# pcbgrado.net
KiCad netlist of a schematic drawn in EAGLE
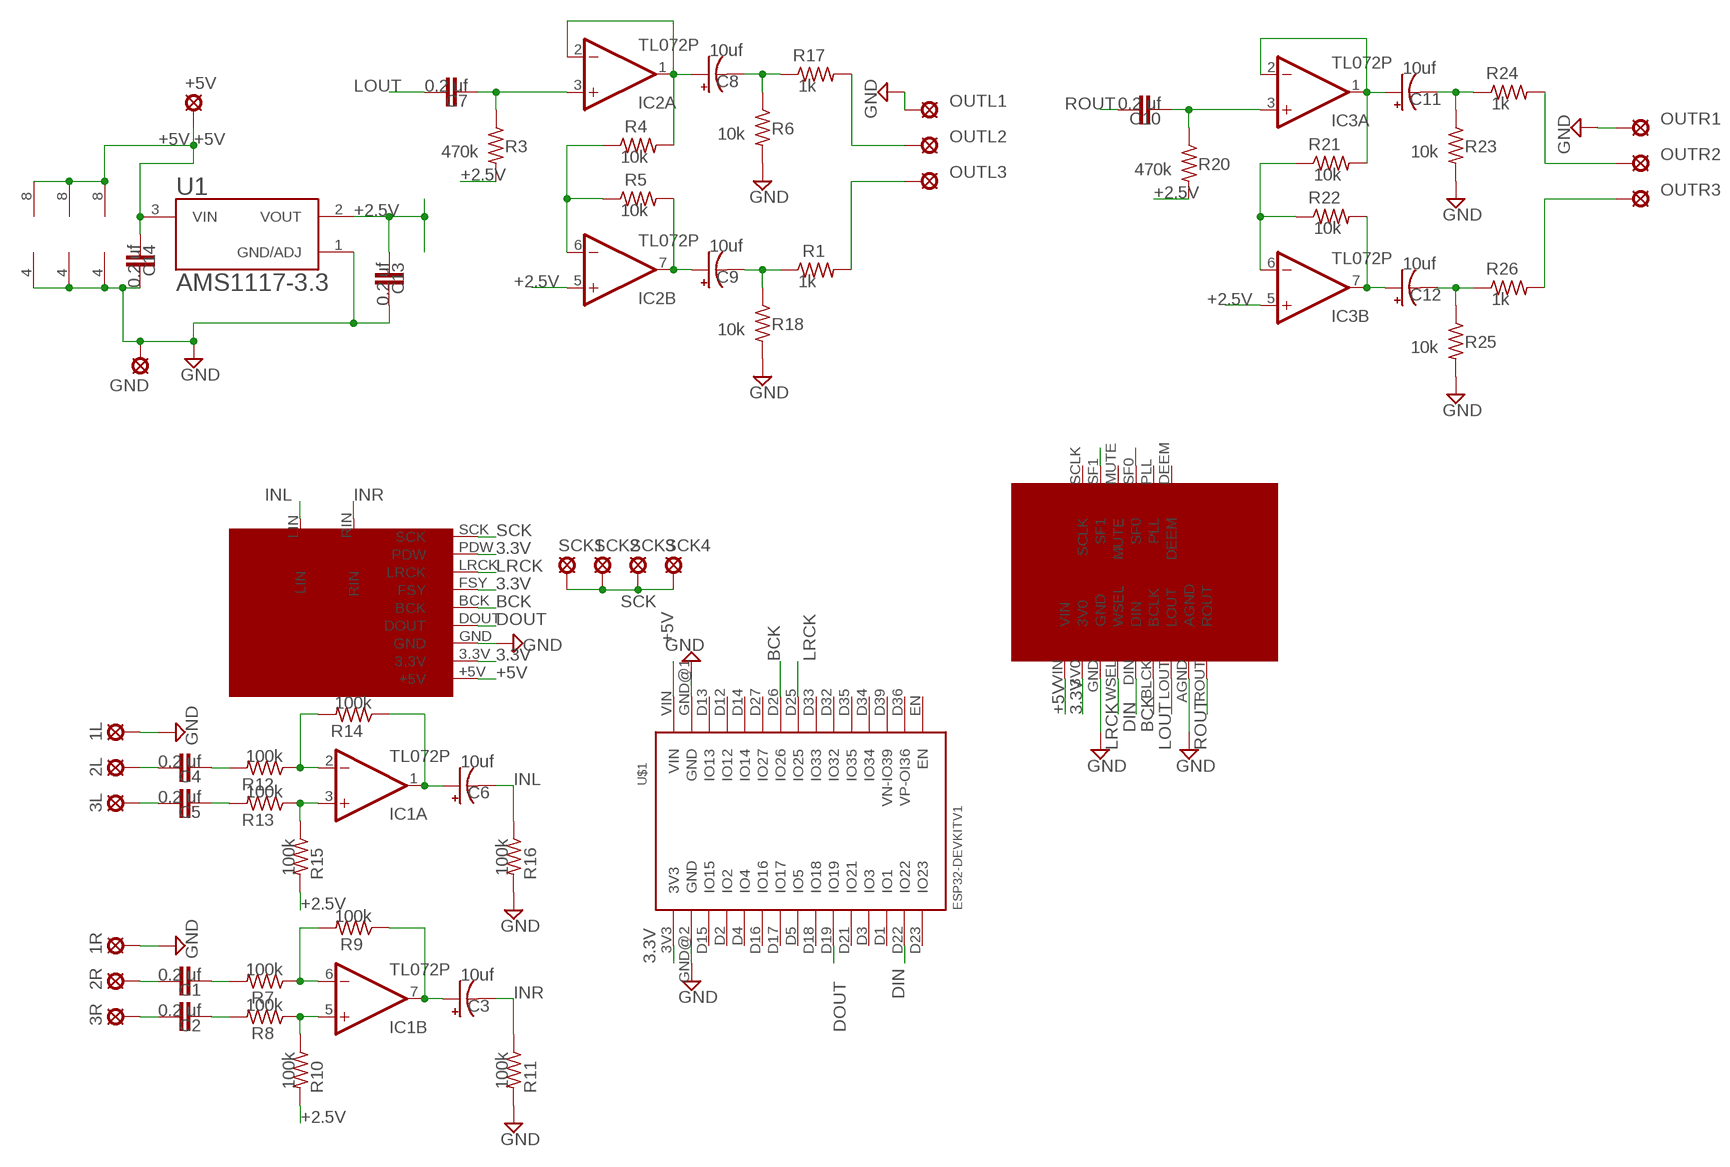
[diagram p0: schematic, sheet 1]

(export (version "E")
  (design (tool "Eeschema 10.0.6"))
  (components
    (comp (ref "+5V")
      (value "LSP10")
      (footprint "eagle-import:LSP10")
      (libsource (lib "eagle-import") (part "LSP10"))
    )
    (comp (ref "1L")
      (value "LSP10")
      (footprint "eagle-import:LSP10")
      (libsource (lib "eagle-import") (part "LSP10"))
    )
    (comp (ref "1R")
      (value "LSP10")
      (footprint "eagle-import:LSP10")
      (libsource (lib "eagle-import") (part "LSP10"))
    )
    (comp (ref "2L")
      (value "LSP10")
      (footprint "eagle-import:LSP10")
      (libsource (lib "eagle-import") (part "LSP10"))
    )
    (comp (ref "2R")
      (value "LSP10")
      (footprint "eagle-import:LSP10")
      (libsource (lib "eagle-import") (part "LSP10"))
    )
    (comp (ref "3L")
      (value "LSP10")
      (footprint "eagle-import:LSP10")
      (libsource (lib "eagle-import") (part "LSP10"))
    )
    (comp (ref "3R")
      (value "LSP10")
      (footprint "eagle-import:LSP10")
      (libsource (lib "eagle-import") (part "LSP10"))
    )
    (comp (ref "C1")
      (value "C-EU025-025X050")
      (footprint "eagle-import:C025-025X050")
      (fields (field (name "POPULARITY") "65") (field (name "POPULARITY_1") "0.2 uf"))
      (libsource (lib "eagle-import") (part "C-EU025-025X050"))
    )
    (comp (ref "C2")
      (value "C-EU025-025X050")
      (footprint "eagle-import:C025-025X050")
      (fields (field (name "POPULARITY") "65") (field (name "POPULARITY_1") "0.2 uf"))
      (libsource (lib "eagle-import") (part "C-EU025-025X050"))
    )
    (comp (ref "C3")
      (value "CPOL-USE1.8-4")
      (footprint "eagle-import:E1,8-4")
      (fields (field (name "POPULARITY") "6") (field (name "POPULARITY_1") "10uf"))
      (libsource (lib "eagle-import") (part "CPOL-USE1.8-4"))
    )
    (comp (ref "C4")
      (value "C-EU025-025X050")
      (footprint "eagle-import:C025-025X050")
      (fields (field (name "POPULARITY") "65") (field (name "POPULARITY_1") "0.2 uf"))
      (libsource (lib "eagle-import") (part "C-EU025-025X050"))
    )
    (comp (ref "C5")
      (value "C-EU025-025X050")
      (footprint "eagle-import:C025-025X050")
      (fields (field (name "POPULARITY") "65") (field (name "POPULARITY_1") "0.2 uf"))
      (libsource (lib "eagle-import") (part "C-EU025-025X050"))
    )
    (comp (ref "C6")
      (value "CPOL-USE1.8-4")
      (footprint "eagle-import:E1,8-4")
      (fields (field (name "POPULARITY") "6") (field (name "POPULARITY_1") "10uf"))
      (libsource (lib "eagle-import") (part "CPOL-USE1.8-4"))
    )
    (comp (ref "C7")
      (value "C-EU025-030X050")
      (footprint "eagle-import:C025-030X050")
      (fields (field (name "POPULARITY") "14") (field (name "POPULARITY_1") "0.2 uf"))
      (libsource (lib "eagle-import") (part "C-EU025-030X050"))
    )
    (comp (ref "C8")
      (value "CPOL-USE1.8-4")
      (footprint "eagle-import:E1,8-4")
      (fields (field (name "POPULARITY") "6") (field (name "POPULARITY_1") "10uf"))
      (libsource (lib "eagle-import") (part "CPOL-USE1.8-4"))
    )
    (comp (ref "C9")
      (value "CPOL-USE1.8-4")
      (footprint "eagle-import:E1,8-4")
      (fields (field (name "POPULARITY") "6") (field (name "POPULARITY_1") "10uf"))
      (libsource (lib "eagle-import") (part "CPOL-USE1.8-4"))
    )
    (comp (ref "C10")
      (value "C-EU025-030X050")
      (footprint "eagle-import:C025-030X050")
      (fields (field (name "POPULARITY") "14") (field (name "POPULARITY_1") "0.2 uf"))
      (libsource (lib "eagle-import") (part "C-EU025-030X050"))
    )
    (comp (ref "C11")
      (value "CPOL-USE1.8-4")
      (footprint "eagle-import:E1,8-4")
      (fields (field (name "POPULARITY") "6") (field (name "POPULARITY_1") "10uf"))
      (libsource (lib "eagle-import") (part "CPOL-USE1.8-4"))
    )
    (comp (ref "C12")
      (value "CPOL-USE1.8-4")
      (footprint "eagle-import:E1,8-4")
      (fields (field (name "POPULARITY") "6") (field (name "POPULARITY_1") "10uf"))
      (libsource (lib "eagle-import") (part "CPOL-USE1.8-4"))
    )
    (comp (ref "C13")
      (value "C-EU025-025X050")
      (footprint "eagle-import:C025-025X050")
      (fields (field (name "POPULARITY") "65") (field (name "POPULARITY_1") "0.2 uf"))
      (libsource (lib "eagle-import") (part "C-EU025-025X050"))
    )
    (comp (ref "C14")
      (value "C-EU025-025X050")
      (footprint "eagle-import:C025-025X050")
      (fields (field (name "POPULARITY") "65") (field (name "POPULARITY_1") "0.2 uf"))
      (libsource (lib "eagle-import") (part "C-EU025-025X050"))
    )
    (comp (ref "GND")
      (value "LSP10")
      (footprint "eagle-import:LSP10")
      (libsource (lib "eagle-import") (part "LSP10"))
    )
    (comp (ref "IC1")
      (value "TL072P")
      (footprint "eagle-import:DIL08")
      (libsource (lib "eagle-import") (part "TL072P"))
    )
    (comp (ref "IC2")
      (value "TL072P")
      (footprint "eagle-import:DIL08")
      (libsource (lib "eagle-import") (part "TL072P"))
    )
    (comp (ref "IC3")
      (value "TL072P")
      (footprint "eagle-import:DIL08")
      (libsource (lib "eagle-import") (part "TL072P"))
    )
    (comp (ref "OUTL1")
      (value "LSP10")
      (footprint "eagle-import:LSP10")
      (libsource (lib "eagle-import") (part "LSP10"))
    )
    (comp (ref "OUTL2")
      (value "LSP10")
      (footprint "eagle-import:LSP10")
      (libsource (lib "eagle-import") (part "LSP10"))
    )
    (comp (ref "OUTL3")
      (value "LSP10")
      (footprint "eagle-import:LSP10")
      (libsource (lib "eagle-import") (part "LSP10"))
    )
    (comp (ref "OUTR1")
      (value "LSP10")
      (footprint "eagle-import:LSP10")
      (libsource (lib "eagle-import") (part "LSP10"))
    )
    (comp (ref "OUTR2")
      (value "LSP10")
      (footprint "eagle-import:LSP10")
      (libsource (lib "eagle-import") (part "LSP10"))
    )
    (comp (ref "OUTR3")
      (value "LSP10")
      (footprint "eagle-import:LSP10")
      (libsource (lib "eagle-import") (part "LSP10"))
    )
    (comp (ref "R1")
      (value "R-US_0204/7")
      (footprint "eagle-import:0204_7")
      (fields (field (name "POPULARITY") "48") (field (name "POPULARITY_1") "1k"))
      (libsource (lib "eagle-import") (part "R-US_0204/7"))
    )
    (comp (ref "R3")
      (value "R-US_0204/7")
      (footprint "eagle-import:0204_7")
      (fields (field (name "POPULARITY") "48") (field (name "POPULARITY_1") "470k"))
      (libsource (lib "eagle-import") (part "R-US_0204/7"))
    )
    (comp (ref "R4")
      (value "R-US_0204/7")
      (footprint "eagle-import:0204_7")
      (fields (field (name "POPULARITY") "48") (field (name "POPULARITY_1") "10k"))
      (libsource (lib "eagle-import") (part "R-US_0204/7"))
    )
    (comp (ref "R5")
      (value "R-US_0204/7")
      (footprint "eagle-import:0204_7")
      (fields (field (name "POPULARITY") "48") (field (name "POPULARITY_1") "10k"))
      (libsource (lib "eagle-import") (part "R-US_0204/7"))
    )
    (comp (ref "R6")
      (value "R-US_0204/7")
      (footprint "eagle-import:0204_7")
      (fields (field (name "POPULARITY") "48") (field (name "POPULARITY_1") "10k"))
      (libsource (lib "eagle-import") (part "R-US_0204/7"))
    )
    (comp (ref "R7")
      (value "R-US_0204/7")
      (footprint "eagle-import:0204_7")
      (fields (field (name "POPULARITY") "48") (field (name "POPULARITY_1") "100k"))
      (libsource (lib "eagle-import") (part "R-US_0204/7"))
    )
    (comp (ref "R8")
      (value "R-US_0204/7")
      (footprint "eagle-import:0204_7")
      (fields (field (name "POPULARITY") "48") (field (name "POPULARITY_1") "100k"))
      (libsource (lib "eagle-import") (part "R-US_0204/7"))
    )
    (comp (ref "R9")
      (value "R-US_0204/7")
      (footprint "eagle-import:0204_7")
      (fields (field (name "POPULARITY") "48") (field (name "POPULARITY_1") "100k"))
      (libsource (lib "eagle-import") (part "R-US_0204/7"))
    )
    (comp (ref "R10")
      (value "R-US_0204/7")
      (footprint "eagle-import:0204_7")
      (fields (field (name "POPULARITY") "48") (field (name "POPULARITY_1") "100k"))
      (libsource (lib "eagle-import") (part "R-US_0204/7"))
    )
    (comp (ref "R11")
      (value "R-US_0204/7")
      (footprint "eagle-import:0204_7")
      (fields (field (name "POPULARITY") "48") (field (name "POPULARITY_1") "100k"))
      (libsource (lib "eagle-import") (part "R-US_0204/7"))
    )
    (comp (ref "R12")
      (value "R-US_0204/7")
      (footprint "eagle-import:0204_7")
      (fields (field (name "POPULARITY") "48") (field (name "POPULARITY_1") "100k"))
      (libsource (lib "eagle-import") (part "R-US_0204/7"))
    )
    (comp (ref "R13")
      (value "R-US_0204/7")
      (footprint "eagle-import:0204_7")
      (fields (field (name "POPULARITY") "48") (field (name "POPULARITY_1") "100k"))
      (libsource (lib "eagle-import") (part "R-US_0204/7"))
    )
    (comp (ref "R14")
      (value "R-US_0204/7")
      (footprint "eagle-import:0204_7")
      (fields (field (name "POPULARITY") "48") (field (name "POPULARITY_1") "100k"))
      (libsource (lib "eagle-import") (part "R-US_0204/7"))
    )
    (comp (ref "R15")
      (value "R-US_0204/7")
      (footprint "eagle-import:0204_7")
      (fields (field (name "POPULARITY") "48") (field (name "POPULARITY_1") "100k"))
      (libsource (lib "eagle-import") (part "R-US_0204/7"))
    )
    (comp (ref "R16")
      (value "R-US_0204/7")
      (footprint "eagle-import:0204_7")
      (fields (field (name "POPULARITY") "48") (field (name "POPULARITY_1") "100k"))
      (libsource (lib "eagle-import") (part "R-US_0204/7"))
    )
    (comp (ref "R17")
      (value "R-US_0204/7")
      (footprint "eagle-import:0204_7")
      (fields (field (name "POPULARITY") "48") (field (name "POPULARITY_1") "1k"))
      (libsource (lib "eagle-import") (part "R-US_0204/7"))
    )
    (comp (ref "R18")
      (value "R-US_0204/7")
      (footprint "eagle-import:0204_7")
      (fields (field (name "POPULARITY") "48") (field (name "POPULARITY_1") "10k"))
      (libsource (lib "eagle-import") (part "R-US_0204/7"))
    )
    (comp (ref "R20")
      (value "R-US_0204/7")
      (footprint "eagle-import:0204_7")
      (fields (field (name "POPULARITY") "48") (field (name "POPULARITY_1") "470k"))
      (libsource (lib "eagle-import") (part "R-US_0204/7"))
    )
    (comp (ref "R21")
      (value "R-US_0204/7")
      (footprint "eagle-import:0204_7")
      (fields (field (name "POPULARITY") "48") (field (name "POPULARITY_1") "10k"))
      (libsource (lib "eagle-import") (part "R-US_0204/7"))
    )
    (comp (ref "R22")
      (value "R-US_0204/7")
      (footprint "eagle-import:0204_7")
      (fields (field (name "POPULARITY") "48") (field (name "POPULARITY_1") "10k"))
      (libsource (lib "eagle-import") (part "R-US_0204/7"))
    )
    (comp (ref "R23")
      (value "R-US_0204/7")
      (footprint "eagle-import:0204_7")
      (fields (field (name "POPULARITY") "48") (field (name "POPULARITY_1") "10k"))
      (libsource (lib "eagle-import") (part "R-US_0204/7"))
    )
    (comp (ref "R24")
      (value "R-US_0204/7")
      (footprint "eagle-import:0204_7")
      (fields (field (name "POPULARITY") "48") (field (name "POPULARITY_1") "1k"))
      (libsource (lib "eagle-import") (part "R-US_0204/7"))
    )
    (comp (ref "R25")
      (value "R-US_0204/7")
      (footprint "eagle-import:0204_7")
      (fields (field (name "POPULARITY") "48") (field (name "POPULARITY_1") "10k"))
      (libsource (lib "eagle-import") (part "R-US_0204/7"))
    )
    (comp (ref "R26")
      (value "R-US_0204/7")
      (footprint "eagle-import:0204_7")
      (fields (field (name "POPULARITY") "48") (field (name "POPULARITY_1") "1k"))
      (libsource (lib "eagle-import") (part "R-US_0204/7"))
    )
    (comp (ref "SCK1")
      (value "LSP10")
      (footprint "eagle-import:LSP10")
      (libsource (lib "eagle-import") (part "LSP10"))
    )
    (comp (ref "SCK2")
      (value "LSP10")
      (footprint "eagle-import:LSP10")
      (libsource (lib "eagle-import") (part "LSP10"))
    )
    (comp (ref "SCK3")
      (value "LSP10")
      (footprint "eagle-import:LSP10")
      (libsource (lib "eagle-import") (part "LSP10"))
    )
    (comp (ref "SCK4")
      (value "LSP10")
      (footprint "eagle-import:LSP10")
      (libsource (lib "eagle-import") (part "LSP10"))
    )
    (comp (ref "U$1")
      (value "ESP32DEVKITV1")
      (footprint "eagle-import:ESP32-DEVKITV1")
      (libsource (lib "eagle-import") (part "ESP32DEVKITV1"))
    )
    (comp (ref "U$2")
      (value "PCM1802DIS")
      (footprint "eagle-import:PCM1802PC")
      (libsource (lib "eagle-import") (part "PCM1802DIS"))
    )
    (comp (ref "U$3")
      (value "UDA1334A")
      (footprint "eagle-import:UDA1334A")
      (libsource (lib "eagle-import") (part "UDA1334A"))
    )
    (comp (ref "U1")
      (value "AMS1117-3.3")
      (footprint "eagle-import:SOT229P700X180-4N")
      (fields (field (name "MF") "Advanced Monolithic Systems"))
      (libsource (lib "eagle-import") (part "AMS1117-3.3"))
    )
  )
  (nets
    (net (code "1") (name "/+2.5V") (class "Default")
      (node (ref "C13") (pin "2") (pinfunction "2_2") (pintype "passive"))
      (node (ref "IC2") (pin "5") (pinfunction "+IN_5") (pintype "input"))
      (node (ref "IC3") (pin "5") (pinfunction "+IN_5") (pintype "input"))
      (node (ref "R10") (pin "2") (pinfunction "2_2") (pintype "passive"))
      (node (ref "R15") (pin "2") (pinfunction "2_2") (pintype "passive"))
      (node (ref "R20") (pin "2") (pinfunction "2_2") (pintype "passive"))
      (node (ref "R3") (pin "2") (pinfunction "2_2") (pintype "passive"))
      (node (ref "U1") (pin "2") (pinfunction "VOUT_2") (pintype "output"))
    )
    (net (code "2") (name "/+5V") (class "Default")
      (node (ref "+5V") (pin "MP") (pinfunction "MP_MP") (pintype "passive"))
      (node (ref "C14") (pin "2") (pinfunction "2_2") (pintype "passive"))
      (node (ref "IC1") (pin "8") (pinfunction "V+_8") (pintype "power_in"))
      (node (ref "IC2") (pin "8") (pinfunction "V+_8") (pintype "power_in"))
      (node (ref "IC3") (pin "8") (pinfunction "V+_8") (pintype "power_in"))
      (node (ref "U$1") (pin "VIN") (pinfunction "VIN_VIN") (pintype "bidirectional"))
      (node (ref "U$2") (pin "+5V") (pinfunction "+5V_+5V") (pintype "bidirectional"))
      (node (ref "U$3") (pin "VIN") (pinfunction "VIN_VIN") (pintype "bidirectional"))
      (node (ref "U1") (pin "3") (pinfunction "VIN_3") (pintype "input"))
    )
    (net (code "3") (name "/3.3V") (class "Default")
      (node (ref "U$1") (pin "3V3") (pinfunction "3V3_3V3") (pintype "bidirectional"))
      (node (ref "U$2") (pin "3.3V") (pinfunction "3.3V_3.3V") (pintype "bidirectional"))
      (node (ref "U$2") (pin "FSY") (pinfunction "FSY_FSY") (pintype "bidirectional"))
      (node (ref "U$2") (pin "PDW") (pinfunction "PDW_PDW") (pintype "bidirectional"))
      (node (ref "U$3") (pin "3V0") (pinfunction "3V0_3V0") (pintype "bidirectional"))
    )
    (net (code "4") (name "/BCK") (class "Default")
      (node (ref "U$1") (pin "D26") (pinfunction "IO26_D26") (pintype "bidirectional"))
      (node (ref "U$2") (pin "BCK") (pinfunction "BCK_BCK") (pintype "bidirectional"))
      (node (ref "U$3") (pin "BLCK") (pinfunction "BCLK_BLCK") (pintype "bidirectional"))
    )
    (net (code "5") (name "/DIN") (class "Default")
      (node (ref "U$1") (pin "D22") (pinfunction "IO22_D22") (pintype "bidirectional"))
      (node (ref "U$3") (pin "DIN") (pinfunction "DIN_DIN") (pintype "bidirectional"))
    )
    (net (code "6") (name "/DOUT") (class "Default")
      (node (ref "U$1") (pin "D19") (pinfunction "IO19_D19") (pintype "bidirectional"))
      (node (ref "U$2") (pin "DOUT") (pinfunction "DOUT_DOUT") (pintype "bidirectional"))
    )
    (net (code "7") (name "/INL") (class "Default")
      (node (ref "C6") (pin "-") (pinfunction "-_-") (pintype "passive"))
      (node (ref "R16") (pin "1") (pinfunction "1_1") (pintype "passive"))
      (node (ref "U$2") (pin "LIN") (pinfunction "LIN_LIN") (pintype "bidirectional"))
    )
    (net (code "8") (name "/INR") (class "Default")
      (node (ref "C3") (pin "-") (pinfunction "-_-") (pintype "passive"))
      (node (ref "R11") (pin "1") (pinfunction "1_1") (pintype "passive"))
      (node (ref "U$2") (pin "RIN") (pinfunction "RIN_RIN") (pintype "bidirectional"))
    )
    (net (code "9") (name "/LOUT") (class "Default")
      (node (ref "C7") (pin "1") (pinfunction "1_1") (pintype "passive"))
      (node (ref "U$3") (pin "LOUT") (pinfunction "LOUT_LOUT") (pintype "bidirectional"))
    )
    (net (code "10") (name "/LRCK") (class "Default")
      (node (ref "U$1") (pin "D25") (pinfunction "IO25_D25") (pintype "bidirectional"))
      (node (ref "U$2") (pin "LRCK") (pinfunction "LRCK_LRCK") (pintype "bidirectional"))
      (node (ref "U$3") (pin "WSEL") (pinfunction "WSEL_WSEL") (pintype "bidirectional"))
    )
    (net (code "11") (name "/ROUT") (class "Default")
      (node (ref "C10") (pin "1") (pinfunction "1_1") (pintype "passive"))
      (node (ref "U$3") (pin "ROUT") (pinfunction "ROUT_ROUT") (pintype "bidirectional"))
    )
    (net (code "12") (name "/SCK") (class "Default")
      (node (ref "SCK1") (pin "MP") (pinfunction "MP_MP") (pintype "passive"))
      (node (ref "SCK2") (pin "MP") (pinfunction "MP_MP") (pintype "passive"))
      (node (ref "SCK3") (pin "MP") (pinfunction "MP_MP") (pintype "passive"))
      (node (ref "SCK4") (pin "MP") (pinfunction "MP_MP") (pintype "passive"))
      (node (ref "U$2") (pin "SCK") (pinfunction "SCK_SCK") (pintype "bidirectional"))
    )
    (net (code "13") (name "GND") (class "Default")
      (node (ref "1L") (pin "MP") (pinfunction "MP_MP") (pintype "passive"))
      (node (ref "1R") (pin "MP") (pinfunction "MP_MP") (pintype "passive"))
      (node (ref "C13") (pin "1") (pinfunction "1_1") (pintype "passive"))
      (node (ref "C14") (pin "1") (pinfunction "1_1") (pintype "passive"))
      (node (ref "GND") (pin "MP") (pinfunction "MP_MP") (pintype "passive"))
      (node (ref "IC1") (pin "4") (pinfunction "V-_4") (pintype "power_in"))
      (node (ref "IC2") (pin "4") (pinfunction "V-_4") (pintype "power_in"))
      (node (ref "IC3") (pin "4") (pinfunction "V-_4") (pintype "power_in"))
      (node (ref "OUTL1") (pin "MP") (pinfunction "MP_MP") (pintype "passive"))
      (node (ref "OUTR1") (pin "MP") (pinfunction "MP_MP") (pintype "passive"))
      (node (ref "R11") (pin "2") (pinfunction "2_2") (pintype "passive"))
      (node (ref "R16") (pin "2") (pinfunction "2_2") (pintype "passive"))
      (node (ref "R18") (pin "2") (pinfunction "2_2") (pintype "passive"))
      (node (ref "R23") (pin "2") (pinfunction "2_2") (pintype "passive"))
      (node (ref "R25") (pin "2") (pinfunction "2_2") (pintype "passive"))
      (node (ref "R6") (pin "2") (pinfunction "2_2") (pintype "passive"))
      (node (ref "U$1") (pin "GND@1") (pinfunction "GND_GND@1") (pintype "bidirectional"))
      (node (ref "U$1") (pin "GND@2") (pinfunction "GND_GND@2") (pintype "bidirectional"))
      (node (ref "U$2") (pin "GND") (pinfunction "GND_GND") (pintype "bidirectional"))
      (node (ref "U$3") (pin "AGND") (pinfunction "AGND_AGND") (pintype "bidirectional"))
      (node (ref "U$3") (pin "GND") (pinfunction "GND_GND") (pintype "bidirectional"))
      (node (ref "U1") (pin "1") (pinfunction "GND/ADJ_1") (pintype "power_in"))
    )
    (net (code "14") (name "Net-(2L-PadMP)") (class "Default")
      (node (ref "2L") (pin "MP") (pinfunction "MP_MP") (pintype "passive"))
      (node (ref "C4") (pin "1") (pinfunction "1_1") (pintype "passive"))
    )
    (net (code "15") (name "Net-(2R-PadMP)") (class "Default")
      (node (ref "2R") (pin "MP") (pinfunction "MP_MP") (pintype "passive"))
      (node (ref "C1") (pin "1") (pinfunction "1_1") (pintype "passive"))
    )
    (net (code "16") (name "Net-(3L-PadMP)") (class "Default")
      (node (ref "3L") (pin "MP") (pinfunction "MP_MP") (pintype "passive"))
      (node (ref "C5") (pin "1") (pinfunction "1_1") (pintype "passive"))
    )
    (net (code "17") (name "Net-(3R-PadMP)") (class "Default")
      (node (ref "3R") (pin "MP") (pinfunction "MP_MP") (pintype "passive"))
      (node (ref "C2") (pin "1") (pinfunction "1_1") (pintype "passive"))
    )
    (net (code "18") (name "Net-(C1-Pad2)") (class "Default")
      (node (ref "C1") (pin "2") (pinfunction "2_2") (pintype "passive"))
      (node (ref "R7") (pin "2") (pinfunction "2_2") (pintype "passive"))
    )
    (net (code "19") (name "Net-(C2-Pad2)") (class "Default")
      (node (ref "C2") (pin "2") (pinfunction "2_2") (pintype "passive"))
      (node (ref "R8") (pin "2") (pinfunction "2_2") (pintype "passive"))
    )
    (net (code "20") (name "Net-(C4-Pad2)") (class "Default")
      (node (ref "C4") (pin "2") (pinfunction "2_2") (pintype "passive"))
      (node (ref "R12") (pin "2") (pinfunction "2_2") (pintype "passive"))
    )
    (net (code "21") (name "Net-(C5-Pad2)") (class "Default")
      (node (ref "C5") (pin "2") (pinfunction "2_2") (pintype "passive"))
      (node (ref "R13") (pin "2") (pinfunction "2_2") (pintype "passive"))
    )
    (net (code "22") (name "Net-(C8-Pad-)") (class "Default")
      (node (ref "C8") (pin "-") (pinfunction "-_-") (pintype "passive"))
      (node (ref "R17") (pin "1") (pinfunction "1_1") (pintype "passive"))
      (node (ref "R6") (pin "1") (pinfunction "1_1") (pintype "passive"))
    )
    (net (code "23") (name "Net-(C9-Pad-)") (class "Default")
      (node (ref "C9") (pin "-") (pinfunction "-_-") (pintype "passive"))
      (node (ref "R1") (pin "1") (pinfunction "1_1") (pintype "passive"))
      (node (ref "R18") (pin "1") (pinfunction "1_1") (pintype "passive"))
    )
    (net (code "24") (name "Net-(C11-Pad-)") (class "Default")
      (node (ref "C11") (pin "-") (pinfunction "-_-") (pintype "passive"))
      (node (ref "R23") (pin "1") (pinfunction "1_1") (pintype "passive"))
      (node (ref "R24") (pin "1") (pinfunction "1_1") (pintype "passive"))
    )
    (net (code "25") (name "Net-(C12-Pad-)") (class "Default")
      (node (ref "C12") (pin "-") (pinfunction "-_-") (pintype "passive"))
      (node (ref "R25") (pin "1") (pinfunction "1_1") (pintype "passive"))
      (node (ref "R26") (pin "1") (pinfunction "1_1") (pintype "passive"))
    )
    (net (code "26") (name "Net-(IC1A-+IN)") (class "Default")
      (node (ref "IC1") (pin "3") (pinfunction "+IN_3") (pintype "input"))
      (node (ref "R13") (pin "1") (pinfunction "1_1") (pintype "passive"))
      (node (ref "R15") (pin "1") (pinfunction "1_1") (pintype "passive"))
    )
    (net (code "27") (name "Net-(IC1A--IN)") (class "Default")
      (node (ref "IC1") (pin "2") (pinfunction "-IN_2") (pintype "input"))
      (node (ref "R12") (pin "1") (pinfunction "1_1") (pintype "passive"))
      (node (ref "R14") (pin "2") (pinfunction "2_2") (pintype "passive"))
    )
    (net (code "28") (name "Net-(IC1A-OUT)") (class "Default")
      (node (ref "C6") (pin "+") (pinfunction "+_+") (pintype "passive"))
      (node (ref "IC1") (pin "1") (pinfunction "OUT_1") (pintype "output"))
      (node (ref "R14") (pin "1") (pinfunction "1_1") (pintype "passive"))
    )
    (net (code "29") (name "Net-(IC1B-+IN)") (class "Default")
      (node (ref "IC1") (pin "5") (pinfunction "+IN_5") (pintype "input"))
      (node (ref "R10") (pin "1") (pinfunction "1_1") (pintype "passive"))
      (node (ref "R8") (pin "1") (pinfunction "1_1") (pintype "passive"))
    )
    (net (code "30") (name "Net-(IC1B--IN)") (class "Default")
      (node (ref "IC1") (pin "6") (pinfunction "-IN_6") (pintype "input"))
      (node (ref "R7") (pin "1") (pinfunction "1_1") (pintype "passive"))
      (node (ref "R9") (pin "2") (pinfunction "2_2") (pintype "passive"))
    )
    (net (code "31") (name "Net-(IC1B-OUT)") (class "Default")
      (node (ref "C3") (pin "+") (pinfunction "+_+") (pintype "passive"))
      (node (ref "IC1") (pin "7") (pinfunction "OUT_7") (pintype "output"))
      (node (ref "R9") (pin "1") (pinfunction "1_1") (pintype "passive"))
    )
    (net (code "32") (name "Net-(IC2A-+IN)") (class "Default")
      (node (ref "C7") (pin "2") (pinfunction "2_2") (pintype "passive"))
      (node (ref "IC2") (pin "3") (pinfunction "+IN_3") (pintype "input"))
      (node (ref "R3") (pin "1") (pinfunction "1_1") (pintype "passive"))
    )
    (net (code "33") (name "Net-(IC2A--IN)") (class "Default")
      (node (ref "C8") (pin "+") (pinfunction "+_+") (pintype "passive"))
      (node (ref "IC2") (pin "1") (pinfunction "OUT_1") (pintype "output"))
      (node (ref "IC2") (pin "2") (pinfunction "-IN_2") (pintype "input"))
      (node (ref "R4") (pin "2") (pinfunction "2_2") (pintype "passive"))
    )
    (net (code "34") (name "Net-(IC2B--IN)") (class "Default")
      (node (ref "IC2") (pin "6") (pinfunction "-IN_6") (pintype "input"))
      (node (ref "R4") (pin "1") (pinfunction "1_1") (pintype "passive"))
      (node (ref "R5") (pin "1") (pinfunction "1_1") (pintype "passive"))
    )
    (net (code "35") (name "Net-(IC2B-OUT)") (class "Default")
      (node (ref "C9") (pin "+") (pinfunction "+_+") (pintype "passive"))
      (node (ref "IC2") (pin "7") (pinfunction "OUT_7") (pintype "output"))
      (node (ref "R5") (pin "2") (pinfunction "2_2") (pintype "passive"))
    )
    (net (code "36") (name "Net-(IC3A-+IN)") (class "Default")
      (node (ref "C10") (pin "2") (pinfunction "2_2") (pintype "passive"))
      (node (ref "IC3") (pin "3") (pinfunction "+IN_3") (pintype "input"))
      (node (ref "R20") (pin "1") (pinfunction "1_1") (pintype "passive"))
    )
    (net (code "37") (name "Net-(IC3A--IN)") (class "Default")
      (node (ref "C11") (pin "+") (pinfunction "+_+") (pintype "passive"))
      (node (ref "IC3") (pin "1") (pinfunction "OUT_1") (pintype "output"))
      (node (ref "IC3") (pin "2") (pinfunction "-IN_2") (pintype "input"))
      (node (ref "R21") (pin "2") (pinfunction "2_2") (pintype "passive"))
    )
    (net (code "38") (name "Net-(IC3B--IN)") (class "Default")
      (node (ref "IC3") (pin "6") (pinfunction "-IN_6") (pintype "input"))
      (node (ref "R21") (pin "1") (pinfunction "1_1") (pintype "passive"))
      (node (ref "R22") (pin "1") (pinfunction "1_1") (pintype "passive"))
    )
    (net (code "39") (name "Net-(IC3B-OUT)") (class "Default")
      (node (ref "C12") (pin "+") (pinfunction "+_+") (pintype "passive"))
      (node (ref "IC3") (pin "7") (pinfunction "OUT_7") (pintype "output"))
      (node (ref "R22") (pin "2") (pinfunction "2_2") (pintype "passive"))
    )
    (net (code "40") (name "Net-(OUTL2-PadMP)") (class "Default")
      (node (ref "OUTL2") (pin "MP") (pinfunction "MP_MP") (pintype "passive"))
      (node (ref "R17") (pin "2") (pinfunction "2_2") (pintype "passive"))
    )
    (net (code "41") (name "Net-(OUTL3-PadMP)") (class "Default")
      (node (ref "OUTL3") (pin "MP") (pinfunction "MP_MP") (pintype "passive"))
      (node (ref "R1") (pin "2") (pinfunction "2_2") (pintype "passive"))
    )
    (net (code "42") (name "Net-(OUTR2-PadMP)") (class "Default")
      (node (ref "OUTR2") (pin "MP") (pinfunction "MP_MP") (pintype "passive"))
      (node (ref "R24") (pin "2") (pinfunction "2_2") (pintype "passive"))
    )
    (net (code "43") (name "Net-(OUTR3-PadMP)") (class "Default")
      (node (ref "OUTR3") (pin "MP") (pinfunction "MP_MP") (pintype "passive"))
      (node (ref "R26") (pin "2") (pinfunction "2_2") (pintype "passive"))
    )
    (net (code "44") (name "unconnected-(U$1-IO1-PadD1)") (class "Default")
      (node (ref "U$1") (pin "D1") (pinfunction "IO1_D1") (pintype "bidirectional"))
    )
    (net (code "45") (name "unconnected-(U$1-IO2-PadD2)") (class "Default")
      (node (ref "U$1") (pin "D2") (pinfunction "IO2_D2") (pintype "bidirectional"))
    )
    (net (code "46") (name "unconnected-(U$1-IO3-PadD3)") (class "Default")
      (node (ref "U$1") (pin "D3") (pinfunction "IO3_D3") (pintype "bidirectional"))
    )
    (net (code "47") (name "unconnected-(U$1-IO4-PadD4)") (class "Default")
      (node (ref "U$1") (pin "D4") (pinfunction "IO4_D4") (pintype "bidirectional"))
    )
    (net (code "48") (name "unconnected-(U$1-IO5-PadD5)") (class "Default")
      (node (ref "U$1") (pin "D5") (pinfunction "IO5_D5") (pintype "bidirectional"))
    )
    (net (code "49") (name "unconnected-(U$1-IO12-PadD12)") (class "Default")
      (node (ref "U$1") (pin "D12") (pinfunction "IO12_D12") (pintype "bidirectional"))
    )
    (net (code "50") (name "unconnected-(U$1-IO13-PadD13)") (class "Default")
      (node (ref "U$1") (pin "D13") (pinfunction "IO13_D13") (pintype "bidirectional"))
    )
    (net (code "51") (name "unconnected-(U$1-IO14-PadD14)") (class "Default")
      (node (ref "U$1") (pin "D14") (pinfunction "IO14_D14") (pintype "bidirectional"))
    )
    (net (code "52") (name "unconnected-(U$1-IO15-PadD15)") (class "Default")
      (node (ref "U$1") (pin "D15") (pinfunction "IO15_D15") (pintype "bidirectional"))
    )
    (net (code "53") (name "unconnected-(U$1-IO16-PadD16)") (class "Default")
      (node (ref "U$1") (pin "D16") (pinfunction "IO16_D16") (pintype "bidirectional"))
    )
    (net (code "54") (name "unconnected-(U$1-IO17-PadD17)") (class "Default")
      (node (ref "U$1") (pin "D17") (pinfunction "IO17_D17") (pintype "bidirectional"))
    )
    (net (code "55") (name "unconnected-(U$1-IO18-PadD18)") (class "Default")
      (node (ref "U$1") (pin "D18") (pinfunction "IO18_D18") (pintype "bidirectional"))
    )
    (net (code "56") (name "unconnected-(U$1-IO21-PadD21)") (class "Default")
      (node (ref "U$1") (pin "D21") (pinfunction "IO21_D21") (pintype "bidirectional"))
    )
    (net (code "57") (name "unconnected-(U$1-IO23-PadD23)") (class "Default")
      (node (ref "U$1") (pin "D23") (pinfunction "IO23_D23") (pintype "bidirectional"))
    )
    (net (code "58") (name "unconnected-(U$1-IO27-PadD27)") (class "Default")
      (node (ref "U$1") (pin "D27") (pinfunction "IO27_D27") (pintype "bidirectional"))
    )
    (net (code "59") (name "unconnected-(U$1-IO32-PadD32)") (class "Default")
      (node (ref "U$1") (pin "D32") (pinfunction "IO32_D32") (pintype "bidirectional"))
    )
    (net (code "60") (name "unconnected-(U$1-IO33-PadD33)") (class "Default")
      (node (ref "U$1") (pin "D33") (pinfunction "IO33_D33") (pintype "bidirectional"))
    )
    (net (code "61") (name "unconnected-(U$1-IO34-PadD34)") (class "Default")
      (node (ref "U$1") (pin "D34") (pinfunction "IO34_D34") (pintype "bidirectional"))
    )
    (net (code "62") (name "unconnected-(U$1-IO35-PadD35)") (class "Default")
      (node (ref "U$1") (pin "D35") (pinfunction "IO35_D35") (pintype "bidirectional"))
    )
    (net (code "63") (name "unconnected-(U$1-PadEN)") (class "Default")
      (node (ref "U$1") (pin "EN") (pinfunction "EN_EN") (pintype "bidirectional"))
    )
    (net (code "64") (name "unconnected-(U$1-VN-IO39-PadD39)") (class "Default")
      (node (ref "U$1") (pin "D39") (pinfunction "VN-IO39_D39") (pintype "bidirectional"))
    )
    (net (code "65") (name "unconnected-(U$1-VP-OI36-PadD36)") (class "Default")
      (node (ref "U$1") (pin "D36") (pinfunction "VP-OI36_D36") (pintype "bidirectional"))
    )
    (net (code "66") (name "unconnected-(U$3-PadDEEM)") (class "Default")
      (node (ref "U$3") (pin "DEEM") (pinfunction "DEEM_DEEM") (pintype "bidirectional"))
    )
    (net (code "67") (name "unconnected-(U$3-PadMUTE)") (class "Default")
      (node (ref "U$3") (pin "MUTE") (pinfunction "MUTE_MUTE") (pintype "bidirectional"))
    )
    (net (code "68") (name "unconnected-(U$3-PadPLL)") (class "Default")
      (node (ref "U$3") (pin "PLL") (pinfunction "PLL_PLL") (pintype "bidirectional"))
    )
    (net (code "69") (name "unconnected-(U$3-PadSCLK)") (class "Default")
      (node (ref "U$3") (pin "SCLK") (pinfunction "SCLK_SCLK") (pintype "bidirectional"))
    )
    (net (code "70") (name "unconnected-(U$3-PadSF0)") (class "Default")
      (node (ref "U$3") (pin "SF0") (pinfunction "SF0_SF0") (pintype "bidirectional"))
    )
    (net (code "71") (name "unconnected-(U$3-PadSF1)") (class "Default")
      (node (ref "U$3") (pin "SF1") (pinfunction "SF1_SF1") (pintype "bidirectional"))
    )
  )
)
